# servoshifter.net
KiCad netlist of a schematic drawn in EAGLE
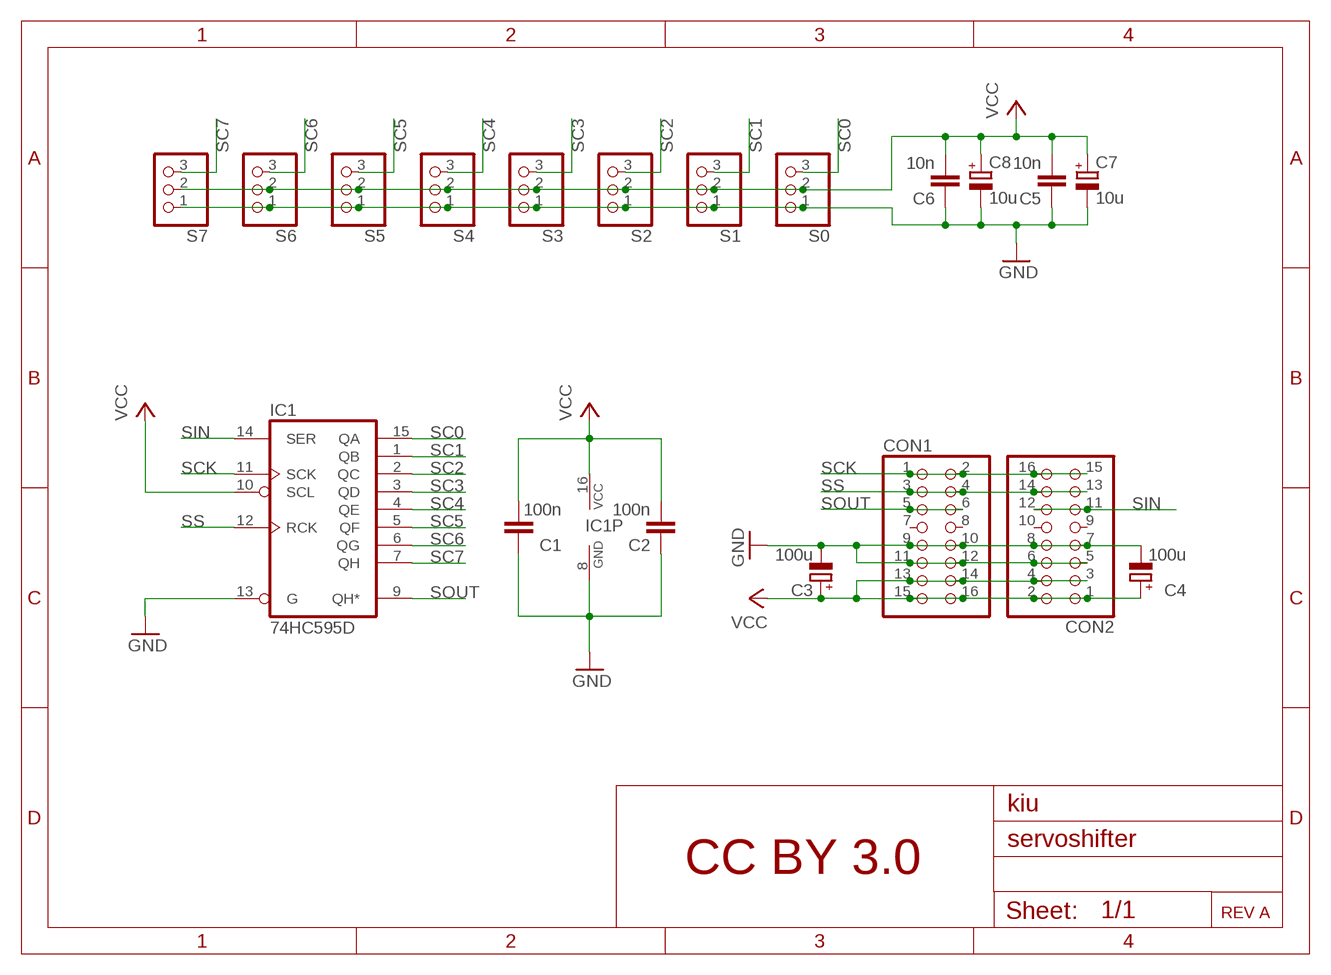
[diagram p0: schematic, sheet 1]

(export (version "E")
  (design (tool "Eeschema 10.0.6"))
  (components
    (comp (ref "C1")
      (value "100n")
      (footprint "eagle-import:C0805")
      (libsource (lib "eagle-import") (part "C-EUC0805"))
    )
    (comp (ref "C2")
      (value "100n")
      (footprint "eagle-import:C0805")
      (libsource (lib "eagle-import") (part "C-EUC0805"))
    )
    (comp (ref "C3")
      (value "100u")
      (footprint "eagle-import:153CLV-0505")
      (libsource (lib "eagle-import") (part "CPOL-EU153CLV-0505"))
    )
    (comp (ref "C4")
      (value "100u")
      (footprint "eagle-import:153CLV-0505")
      (libsource (lib "eagle-import") (part "CPOL-EU153CLV-0505"))
    )
    (comp (ref "C5")
      (value "10n")
      (footprint "eagle-import:C0805")
      (libsource (lib "eagle-import") (part "C-EUC0805"))
    )
    (comp (ref "C6")
      (value "10n")
      (footprint "eagle-import:C0805")
      (libsource (lib "eagle-import") (part "C-EUC0805"))
    )
    (comp (ref "C7")
      (value "10u")
      (footprint "eagle-import:153CLV-0405")
      (libsource (lib "eagle-import") (part "CPOL-EU153CLV-0405"))
    )
    (comp (ref "C8")
      (value "10u")
      (footprint "eagle-import:153CLV-0405")
      (libsource (lib "eagle-import") (part "CPOL-EU153CLV-0405"))
    )
    (comp (ref "CON1")
      (value "PINHD-2X8")
      (footprint "eagle-import:2X08")
      (libsource (lib "eagle-import") (part "PINHD-2X8"))
    )
    (comp (ref "CON2")
      (value "PINHD-2X8")
      (footprint "eagle-import:2X08")
      (libsource (lib "eagle-import") (part "PINHD-2X8"))
    )
    (comp (ref "IC1")
      (value "74HC595D")
      (footprint "eagle-import:SO16")
      (libsource (lib "eagle-import") (part "74595DHC"))
    )
    (comp (ref "S0")
      (value "PINHD-1X3")
      (footprint "eagle-import:1X03")
      (libsource (lib "eagle-import") (part "PINHD-1X3"))
    )
    (comp (ref "S1")
      (value "PINHD-1X3")
      (footprint "eagle-import:1X03")
      (libsource (lib "eagle-import") (part "PINHD-1X3"))
    )
    (comp (ref "S2")
      (value "PINHD-1X3")
      (footprint "eagle-import:1X03")
      (libsource (lib "eagle-import") (part "PINHD-1X3"))
    )
    (comp (ref "S3")
      (value "PINHD-1X3")
      (footprint "eagle-import:1X03")
      (libsource (lib "eagle-import") (part "PINHD-1X3"))
    )
    (comp (ref "S4")
      (value "PINHD-1X3")
      (footprint "eagle-import:1X03")
      (libsource (lib "eagle-import") (part "PINHD-1X3"))
    )
    (comp (ref "S5")
      (value "PINHD-1X3")
      (footprint "eagle-import:1X03")
      (libsource (lib "eagle-import") (part "PINHD-1X3"))
    )
    (comp (ref "S6")
      (value "PINHD-1X3")
      (footprint "eagle-import:1X03")
      (libsource (lib "eagle-import") (part "PINHD-1X3"))
    )
    (comp (ref "S7")
      (value "PINHD-1X3")
      (footprint "eagle-import:1X03")
      (libsource (lib "eagle-import") (part "PINHD-1X3"))
    )
  )
  (nets
    (net (code "1") (name "/SC0") (class "Default")
      (node (ref "IC1") (pin "15") (pinfunction "QA_15") (pintype "tri_state"))
      (node (ref "S0") (pin "3") (pinfunction "3_3") (pintype "passive"))
    )
    (net (code "2") (name "/SC1") (class "Default")
      (node (ref "IC1") (pin "1") (pinfunction "QB_1") (pintype "tri_state"))
      (node (ref "S1") (pin "3") (pinfunction "3_3") (pintype "passive"))
    )
    (net (code "3") (name "/SC2") (class "Default")
      (node (ref "IC1") (pin "2") (pinfunction "QC_2") (pintype "tri_state"))
      (node (ref "S2") (pin "3") (pinfunction "3_3") (pintype "passive"))
    )
    (net (code "4") (name "/SC3") (class "Default")
      (node (ref "IC1") (pin "3") (pinfunction "QD_3") (pintype "tri_state"))
      (node (ref "S3") (pin "3") (pinfunction "3_3") (pintype "passive"))
    )
    (net (code "5") (name "/SC4") (class "Default")
      (node (ref "IC1") (pin "4") (pinfunction "QE_4") (pintype "tri_state"))
      (node (ref "S4") (pin "3") (pinfunction "3_3") (pintype "passive"))
    )
    (net (code "6") (name "/SC5") (class "Default")
      (node (ref "IC1") (pin "5") (pinfunction "QF_5") (pintype "tri_state"))
      (node (ref "S5") (pin "3") (pinfunction "3_3") (pintype "passive"))
    )
    (net (code "7") (name "/SC6") (class "Default")
      (node (ref "IC1") (pin "6") (pinfunction "QG_6") (pintype "tri_state"))
      (node (ref "S6") (pin "3") (pinfunction "3_3") (pintype "passive"))
    )
    (net (code "8") (name "/SC7") (class "Default")
      (node (ref "IC1") (pin "7") (pinfunction "QH_7") (pintype "tri_state"))
      (node (ref "S7") (pin "3") (pinfunction "3_3") (pintype "passive"))
    )
    (net (code "9") (name "/SCK") (class "Default")
      (node (ref "CON1") (pin "1") (pinfunction "1_1") (pintype "passive"))
      (node (ref "CON1") (pin "2") (pinfunction "2_2") (pintype "passive"))
      (node (ref "CON2") (pin "15") (pinfunction "15_15") (pintype "passive"))
      (node (ref "CON2") (pin "16") (pinfunction "16_16") (pintype "passive"))
      (node (ref "IC1") (pin "11") (pinfunction "SCK_11") (pintype "input"))
    )
    (net (code "10") (name "/SIN") (class "Default")
      (node (ref "CON2") (pin "11") (pinfunction "11_11") (pintype "passive"))
      (node (ref "CON2") (pin "12") (pinfunction "12_12") (pintype "passive"))
      (node (ref "IC1") (pin "14") (pinfunction "SER_14") (pintype "input"))
    )
    (net (code "11") (name "/SOUT") (class "Default")
      (node (ref "CON1") (pin "5") (pinfunction "5_5") (pintype "passive"))
      (node (ref "CON1") (pin "6") (pinfunction "6_6") (pintype "passive"))
      (node (ref "IC1") (pin "9") (pinfunction "QH*_9") (pintype "tri_state"))
    )
    (net (code "12") (name "/SS") (class "Default")
      (node (ref "CON1") (pin "3") (pinfunction "3_3") (pintype "passive"))
      (node (ref "CON1") (pin "4") (pinfunction "4_4") (pintype "passive"))
      (node (ref "CON2") (pin "13") (pinfunction "13_13") (pintype "passive"))
      (node (ref "CON2") (pin "14") (pinfunction "14_14") (pintype "passive"))
      (node (ref "IC1") (pin "12") (pinfunction "RCK_12") (pintype "input"))
    )
    (net (code "13") (name "GND") (class "Default")
      (node (ref "C1") (pin "1") (pinfunction "1_1") (pintype "passive"))
      (node (ref "C2") (pin "1") (pinfunction "1_1") (pintype "passive"))
      (node (ref "C3") (pin "-") (pinfunction "-_-") (pintype "passive"))
      (node (ref "C4") (pin "-") (pinfunction "-_-") (pintype "passive"))
      (node (ref "C5") (pin "1") (pinfunction "1_1") (pintype "passive"))
      (node (ref "C6") (pin "1") (pinfunction "1_1") (pintype "passive"))
      (node (ref "C7") (pin "-") (pinfunction "-_-") (pintype "passive"))
      (node (ref "C8") (pin "-") (pinfunction "-_-") (pintype "passive"))
      (node (ref "CON1") (pin "10") (pinfunction "10_10") (pintype "passive"))
      (node (ref "CON1") (pin "11") (pinfunction "11_11") (pintype "passive"))
      (node (ref "CON1") (pin "12") (pinfunction "12_12") (pintype "passive"))
      (node (ref "CON1") (pin "9") (pinfunction "9_9") (pintype "passive"))
      (node (ref "CON2") (pin "5") (pinfunction "5_5") (pintype "passive"))
      (node (ref "CON2") (pin "6") (pinfunction "6_6") (pintype "passive"))
      (node (ref "CON2") (pin "7") (pinfunction "7_7") (pintype "passive"))
      (node (ref "CON2") (pin "8") (pinfunction "8_8") (pintype "passive"))
      (node (ref "IC1") (pin "13") (pinfunction "G_13") (pintype "input"))
      (node (ref "IC1") (pin "8") (pinfunction "GND_8") (pintype "power_in"))
      (node (ref "S0") (pin "1") (pinfunction "1_1") (pintype "passive"))
      (node (ref "S1") (pin "1") (pinfunction "1_1") (pintype "passive"))
      (node (ref "S2") (pin "1") (pinfunction "1_1") (pintype "passive"))
      (node (ref "S3") (pin "1") (pinfunction "1_1") (pintype "passive"))
      (node (ref "S4") (pin "1") (pinfunction "1_1") (pintype "passive"))
      (node (ref "S5") (pin "1") (pinfunction "1_1") (pintype "passive"))
      (node (ref "S6") (pin "1") (pinfunction "1_1") (pintype "passive"))
      (node (ref "S7") (pin "1") (pinfunction "1_1") (pintype "passive"))
    )
    (net (code "14") (name "VCC") (class "Default")
      (node (ref "C1") (pin "2") (pinfunction "2_2") (pintype "passive"))
      (node (ref "C2") (pin "2") (pinfunction "2_2") (pintype "passive"))
      (node (ref "C3") (pin "+") (pinfunction "+_+") (pintype "passive"))
      (node (ref "C4") (pin "+") (pinfunction "+_+") (pintype "passive"))
      (node (ref "C5") (pin "2") (pinfunction "2_2") (pintype "passive"))
      (node (ref "C6") (pin "2") (pinfunction "2_2") (pintype "passive"))
      (node (ref "C7") (pin "+") (pinfunction "+_+") (pintype "passive"))
      (node (ref "C8") (pin "+") (pinfunction "+_+") (pintype "passive"))
      (node (ref "CON1") (pin "13") (pinfunction "13_13") (pintype "passive"))
      (node (ref "CON1") (pin "14") (pinfunction "14_14") (pintype "passive"))
      (node (ref "CON1") (pin "15") (pinfunction "15_15") (pintype "passive"))
      (node (ref "CON1") (pin "16") (pinfunction "16_16") (pintype "passive"))
      (node (ref "CON2") (pin "1") (pinfunction "1_1") (pintype "passive"))
      (node (ref "CON2") (pin "2") (pinfunction "2_2") (pintype "passive"))
      (node (ref "CON2") (pin "3") (pinfunction "3_3") (pintype "passive"))
      (node (ref "CON2") (pin "4") (pinfunction "4_4") (pintype "passive"))
      (node (ref "IC1") (pin "10") (pinfunction "SCL_10") (pintype "input"))
      (node (ref "IC1") (pin "16") (pinfunction "VCC_16") (pintype "power_in"))
      (node (ref "S0") (pin "2") (pinfunction "2_2") (pintype "passive"))
      (node (ref "S1") (pin "2") (pinfunction "2_2") (pintype "passive"))
      (node (ref "S2") (pin "2") (pinfunction "2_2") (pintype "passive"))
      (node (ref "S3") (pin "2") (pinfunction "2_2") (pintype "passive"))
      (node (ref "S4") (pin "2") (pinfunction "2_2") (pintype "passive"))
      (node (ref "S5") (pin "2") (pinfunction "2_2") (pintype "passive"))
      (node (ref "S6") (pin "2") (pinfunction "2_2") (pintype "passive"))
      (node (ref "S7") (pin "2") (pinfunction "2_2") (pintype "passive"))
    )
    (net (code "15") (name "unconnected-(CON1-Pad7)") (class "Default")
      (node (ref "CON1") (pin "7") (pinfunction "7_7") (pintype "passive"))
    )
    (net (code "16") (name "unconnected-(CON1-Pad8)") (class "Default")
      (node (ref "CON1") (pin "8") (pinfunction "8_8") (pintype "passive"))
    )
    (net (code "17") (name "unconnected-(CON2-Pad9)") (class "Default")
      (node (ref "CON2") (pin "9") (pinfunction "9_9") (pintype "passive"))
    )
    (net (code "18") (name "unconnected-(CON2-Pad10)") (class "Default")
      (node (ref "CON2") (pin "10") (pinfunction "10_10") (pintype "passive"))
    )
  )
)
